# NRF24L01.net
KiCad netlist of a schematic drawn in Altium Designer
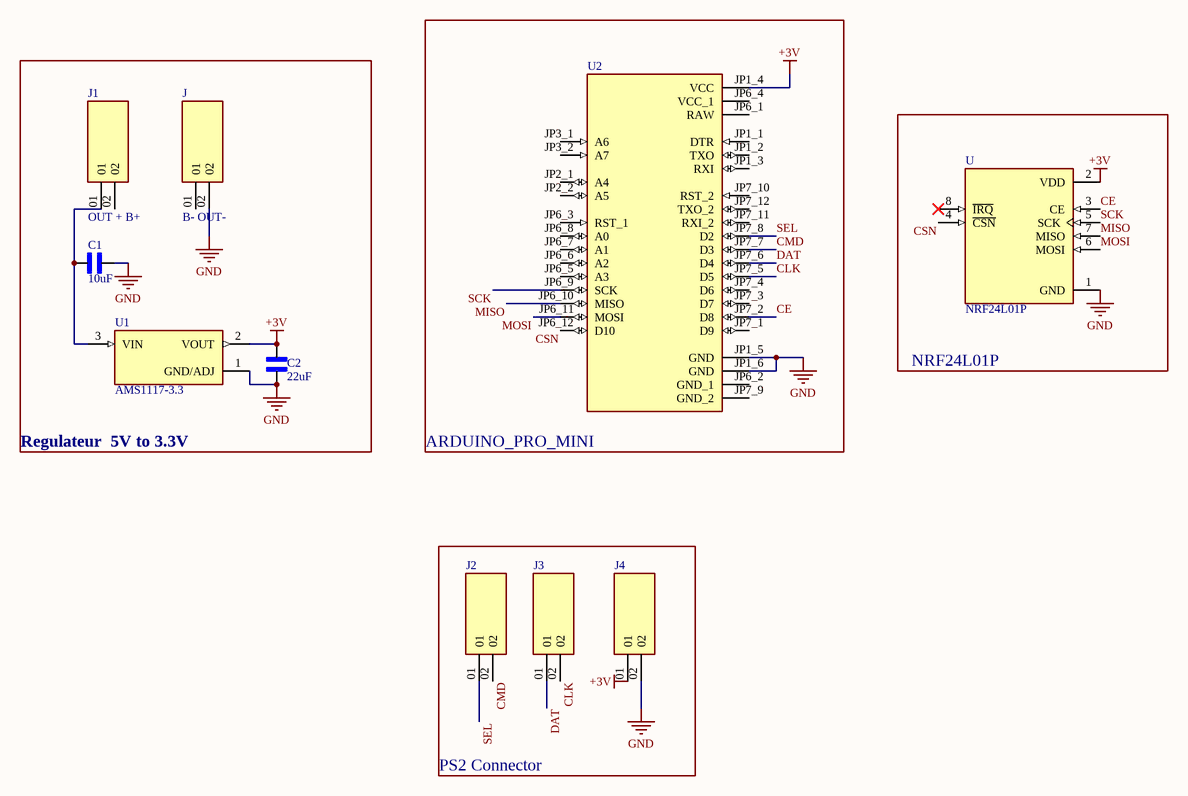
[diagram p0: NRF24L01.SchDoc]

(export (version "E")
  (design (tool "Eeschema 10.0.6"))
  (components
    (comp (ref "C1")
      (value "10uF")
      (footprint "CAPC1608X100N")
      (description "SMD Capacitor X5R(EIA) with Capacitance: 10uF Tol. 20%. Rated Voltage: 25Vdc")
      (fields (field (name "MF") "Murata") (field (name "MP") "GRM188R61E106MA73J"))
      (libsource (lib "10uF") (part "GRM188R61E106MA73J"))
    )
    (comp (ref "C2")
      (value "22uF")
      (footprint "CAPC2012X145N")
      (description "SMD capacitor X5R(EIA) with capacitance 22uF Tol.20%. Rated voltage 10Vdc 85C")
      (fields (field (name "MF") "Murata Electronics") (field (name "MP") "GRM21BR61A226ME44L"))
      (libsource (lib "22uF") (part "GRM21BR61A226ME44L"))
    )
    (comp (ref "J")
      (value "B- OUT-")
      (footprint "pin:SAMTEC_ZW-02-10-T-S-316-236")
      (fields (field (name "MP") "ZW-02-10-T-S-316-236"))
      (libsource (lib "pin") (part "ZW-02-10-T-S-316-236"))
    )
    (comp (ref "J1")
      (value "OUT + B+")
      (footprint "SAMTEC_ZW-02-10-T-S-316-236")
      (fields (field (name "MP") "ZW-02-10-T-S-316-236"))
      (libsource (lib "pin") (part "ZW-02-10-T-S-316-236"))
    )
    (comp (ref "J2")
      (value "SCL CMD")
      (footprint "pin:SAMTEC_ZW-02-10-T-S-316-236")
      (fields (field (name "MP") "ZW-02-10-T-S-316-236"))
      (libsource (lib "pin") (part "ZW-02-10-T-S-316-236"))
    )
    (comp (ref "J3")
      (value "DAT CLK")
      (footprint "pin:SAMTEC_ZW-02-10-T-S-316-236")
      (fields (field (name "MP") "ZW-02-10-T-S-316-236"))
      (libsource (lib "pin") (part "ZW-02-10-T-S-316-236"))
    )
    (comp (ref "J4")
      (value "3.3V GND")
      (footprint "pin:SAMTEC_ZW-02-10-T-S-316-236")
      (fields (field (name "MP") "ZW-02-10-T-S-316-236"))
      (libsource (lib "pin") (part "ZW-02-10-T-S-316-236"))
    )
    (comp (ref "U")
      (value "NRF24L01P")
      (footprint "XCVR_NRF24L01P-MODULE-PCB:XCVR_NRF24L01P-MODULE-PCB")
      (description "- Transceiver For Use With nRF24L01+")
      (fields (field (name "MP") "NRF24L01P-MODULE-PCB") (field (name "MF") "Nordic Semiconductor"))
      (libsource (lib "NRF24L01P-MODULE-PCB") (part "NRF24L01P-MODULE-PCB"))
    )
    (comp (ref "U1")
      (value "AMS1117-3.3")
      (footprint "SOT229P700X180-4N")
      (description "Sot223/Pkg 1-Amp 3.3-Volt Low Drop Out Voltage Regulatator")
      (fields (field (name "MF") "Advanced Monolithic Systems"))
      (libsource (lib "AMS1117-3.3") (part "AMS1117-3.3"))
    )
    (comp (ref "U2")
      (value "ARDUINO_PRO_MINI")
      (footprint "MODULE_ARDUINO_PRO_MINI")
      (fields (field (name "MF") "Arduino") (field (name "MP") "Arduino Pro Mini"))
      (libsource (lib "ARDUINO_PRO_MINI") (part "ARDUINO_PRO_MINI"))
    )
  )
  (nets
    (net (code "1") (name "+3V") (class "Default")
      (node (ref "C2") (pin "2") (pinfunction "2_2") (pintype "passive"))
      (node (ref "J4") (pin "01") (pinfunction "01_01") (pintype "passive"))
      (node (ref "U") (pin "2") (pinfunction "VDD_2") (pintype "power_in"))
      (node (ref "U1") (pin "2") (pinfunction "VOUT_2") (pintype "output"))
      (node (ref "U2") (pin "JP1_4") (pinfunction "VCC_JP1_4") (pintype "power_in"))
    )
    (net (code "2") (name "/CE") (class "Default")
      (node (ref "U") (pin "3") (pinfunction "CE_3") (pintype "input"))
      (node (ref "U2") (pin "JP7_2") (pinfunction "D8_JP7_2") (pintype "bidirectional"))
    )
    (net (code "3") (name "/CLK") (class "Default")
      (node (ref "J3") (pin "02") (pinfunction "02_02") (pintype "passive"))
      (node (ref "U2") (pin "JP7_5") (pinfunction "D5_JP7_5") (pintype "bidirectional"))
    )
    (net (code "4") (name "/CMD") (class "Default")
      (node (ref "J2") (pin "02") (pinfunction "02_02") (pintype "passive"))
      (node (ref "U2") (pin "JP7_7") (pinfunction "D3_JP7_7") (pintype "bidirectional"))
    )
    (net (code "5") (name "/CSN") (class "Default")
      (node (ref "U") (pin "4") (pinfunction "~{CSN}_4") (pintype "input"))
      (node (ref "U2") (pin "JP6_12") (pinfunction "D10_JP6_12") (pintype "bidirectional"))
    )
    (net (code "6") (name "/DAT") (class "Default")
      (node (ref "J3") (pin "01") (pinfunction "01_01") (pintype "passive"))
      (node (ref "U2") (pin "JP7_6") (pinfunction "D4_JP7_6") (pintype "bidirectional"))
    )
    (net (code "7") (name "/MISO") (class "Default")
      (node (ref "U") (pin "7") (pinfunction "MISO_7") (pintype "input"))
      (node (ref "U2") (pin "JP6_10") (pinfunction "MISO_JP6_10") (pintype "bidirectional"))
    )
    (net (code "8") (name "/MOSI") (class "Default")
      (node (ref "U") (pin "6") (pinfunction "MOSI_6") (pintype "input"))
      (node (ref "U2") (pin "JP6_11") (pinfunction "MOSI_JP6_11") (pintype "bidirectional"))
    )
    (net (code "9") (name "/SCK") (class "Default")
      (node (ref "U") (pin "5") (pinfunction "SCK_5") (pintype "input"))
      (node (ref "U2") (pin "JP6_9") (pinfunction "SCK_JP6_9") (pintype "bidirectional"))
    )
    (net (code "10") (name "/SEL") (class "Default")
      (node (ref "J2") (pin "01") (pinfunction "01_01") (pintype "passive"))
      (node (ref "U2") (pin "JP7_8") (pinfunction "D2_JP7_8") (pintype "bidirectional"))
    )
    (net (code "11") (name "GND") (class "Default")
      (node (ref "C1") (pin "1") (pinfunction "1_1") (pintype "passive"))
      (node (ref "C2") (pin "1") (pinfunction "1_1") (pintype "passive"))
      (node (ref "J") (pin "02") (pinfunction "02_02") (pintype "passive"))
      (node (ref "J4") (pin "02") (pinfunction "02_02") (pintype "passive"))
      (node (ref "U") (pin "1") (pinfunction "GND_1") (pintype "power_in"))
      (node (ref "U1") (pin "1") (pinfunction "GND/ADJ_1") (pintype "power_in"))
      (node (ref "U2") (pin "JP1_5") (pinfunction "GND_JP1_5") (pintype "power_in"))
      (node (ref "U2") (pin "JP1_6") (pinfunction "GND_JP1_6") (pintype "power_in"))
    )
    (net (code "12") (name "Net-(U1-VIN)") (class "Default")
      (node (ref "C1") (pin "2") (pinfunction "2_2") (pintype "passive"))
      (node (ref "J1") (pin "01") (pinfunction "01_01") (pintype "passive"))
      (node (ref "U1") (pin "3") (pinfunction "VIN_3") (pintype "input"))
    )
    (net (code "13") (name "unconnected-(J-Pad01)") (class "Default")
      (node (ref "J") (pin "01") (pinfunction "01_01") (pintype "passive"))
    )
    (net (code "14") (name "unconnected-(J1-Pad02)") (class "Default")
      (node (ref "J1") (pin "02") (pinfunction "02_02") (pintype "passive"))
    )
    (net (code "15") (name "unconnected-(U-~{IRQ}-Pad8)") (class "Default")
      (node (ref "U") (pin "8") (pinfunction "~{IRQ}_8") (pintype "input+no_connect"))
    )
    (net (code "16") (name "unconnected-(U2-A0-PadJP6_8)") (class "Default")
      (node (ref "U2") (pin "JP6_8") (pinfunction "A0_JP6_8") (pintype "bidirectional"))
    )
    (net (code "17") (name "unconnected-(U2-A1-PadJP6_7)") (class "Default")
      (node (ref "U2") (pin "JP6_7") (pinfunction "A1_JP6_7") (pintype "bidirectional"))
    )
    (net (code "18") (name "unconnected-(U2-A2-PadJP6_6)") (class "Default")
      (node (ref "U2") (pin "JP6_6") (pinfunction "A2_JP6_6") (pintype "bidirectional"))
    )
    (net (code "19") (name "unconnected-(U2-A3-PadJP6_5)") (class "Default")
      (node (ref "U2") (pin "JP6_5") (pinfunction "A3_JP6_5") (pintype "bidirectional"))
    )
    (net (code "20") (name "unconnected-(U2-A4-PadJP2_1)") (class "Default")
      (node (ref "U2") (pin "JP2_1") (pinfunction "A4_JP2_1") (pintype "bidirectional"))
    )
    (net (code "21") (name "unconnected-(U2-A5-PadJP2_2)") (class "Default")
      (node (ref "U2") (pin "JP2_2") (pinfunction "A5_JP2_2") (pintype "bidirectional"))
    )
    (net (code "22") (name "unconnected-(U2-A6-PadJP3_1)") (class "Default")
      (node (ref "U2") (pin "JP3_1") (pinfunction "A6_JP3_1") (pintype "input"))
    )
    (net (code "23") (name "unconnected-(U2-A7-PadJP3_2)") (class "Default")
      (node (ref "U2") (pin "JP3_2") (pinfunction "A7_JP3_2") (pintype "input"))
    )
    (net (code "24") (name "unconnected-(U2-D6-PadJP7_4)") (class "Default")
      (node (ref "U2") (pin "JP7_4") (pinfunction "D6_JP7_4") (pintype "bidirectional"))
    )
    (net (code "25") (name "unconnected-(U2-D7-PadJP7_3)") (class "Default")
      (node (ref "U2") (pin "JP7_3") (pinfunction "D7_JP7_3") (pintype "bidirectional"))
    )
    (net (code "26") (name "unconnected-(U2-D9-PadJP7_1)") (class "Default")
      (node (ref "U2") (pin "JP7_1") (pinfunction "D9_JP7_1") (pintype "bidirectional"))
    )
    (net (code "27") (name "unconnected-(U2-DTR-PadJP1_1)") (class "Default")
      (node (ref "U2") (pin "JP1_1") (pinfunction "DTR_JP1_1") (pintype "input"))
    )
    (net (code "28") (name "unconnected-(U2-GND_1-PadJP6_2)") (class "Default")
      (node (ref "U2") (pin "JP6_2") (pinfunction "GND_1_JP6_2") (pintype "power_in"))
    )
    (net (code "29") (name "unconnected-(U2-GND_2-PadJP7_9)") (class "Default")
      (node (ref "U2") (pin "JP7_9") (pinfunction "GND_2_JP7_9") (pintype "power_in"))
    )
    (net (code "30") (name "unconnected-(U2-RAW-PadJP6_1)") (class "Default")
      (node (ref "U2") (pin "JP6_1") (pinfunction "RAW_JP6_1") (pintype "power_in"))
    )
    (net (code "31") (name "unconnected-(U2-RST_1-PadJP6_3)") (class "Default")
      (node (ref "U2") (pin "JP6_3") (pinfunction "RST_1_JP6_3") (pintype "input"))
    )
    (net (code "32") (name "unconnected-(U2-RST_2-PadJP7_10)") (class "Default")
      (node (ref "U2") (pin "JP7_10") (pinfunction "RST_2_JP7_10") (pintype "input"))
    )
    (net (code "33") (name "unconnected-(U2-RXI-PadJP1_3)") (class "Default")
      (node (ref "U2") (pin "JP1_3") (pinfunction "RXI_JP1_3") (pintype "bidirectional"))
    )
    (net (code "34") (name "unconnected-(U2-RXI_2-PadJP7_11)") (class "Default")
      (node (ref "U2") (pin "JP7_11") (pinfunction "RXI_2_JP7_11") (pintype "bidirectional"))
    )
    (net (code "35") (name "unconnected-(U2-TXO-PadJP1_2)") (class "Default")
      (node (ref "U2") (pin "JP1_2") (pinfunction "TXO_JP1_2") (pintype "bidirectional"))
    )
    (net (code "36") (name "unconnected-(U2-TXO_2-PadJP7_12)") (class "Default")
      (node (ref "U2") (pin "JP7_12") (pinfunction "TXO_2_JP7_12") (pintype "bidirectional"))
    )
    (net (code "37") (name "unconnected-(U2-VCC_1-PadJP6_4)") (class "Default")
      (node (ref "U2") (pin "JP6_4") (pinfunction "VCC_1_JP6_4") (pintype "power_in"))
    )
  )
)
